# STorM32_BGC_mpu_module_v008.net
KiCad netlist of a schematic drawn in EAGLE
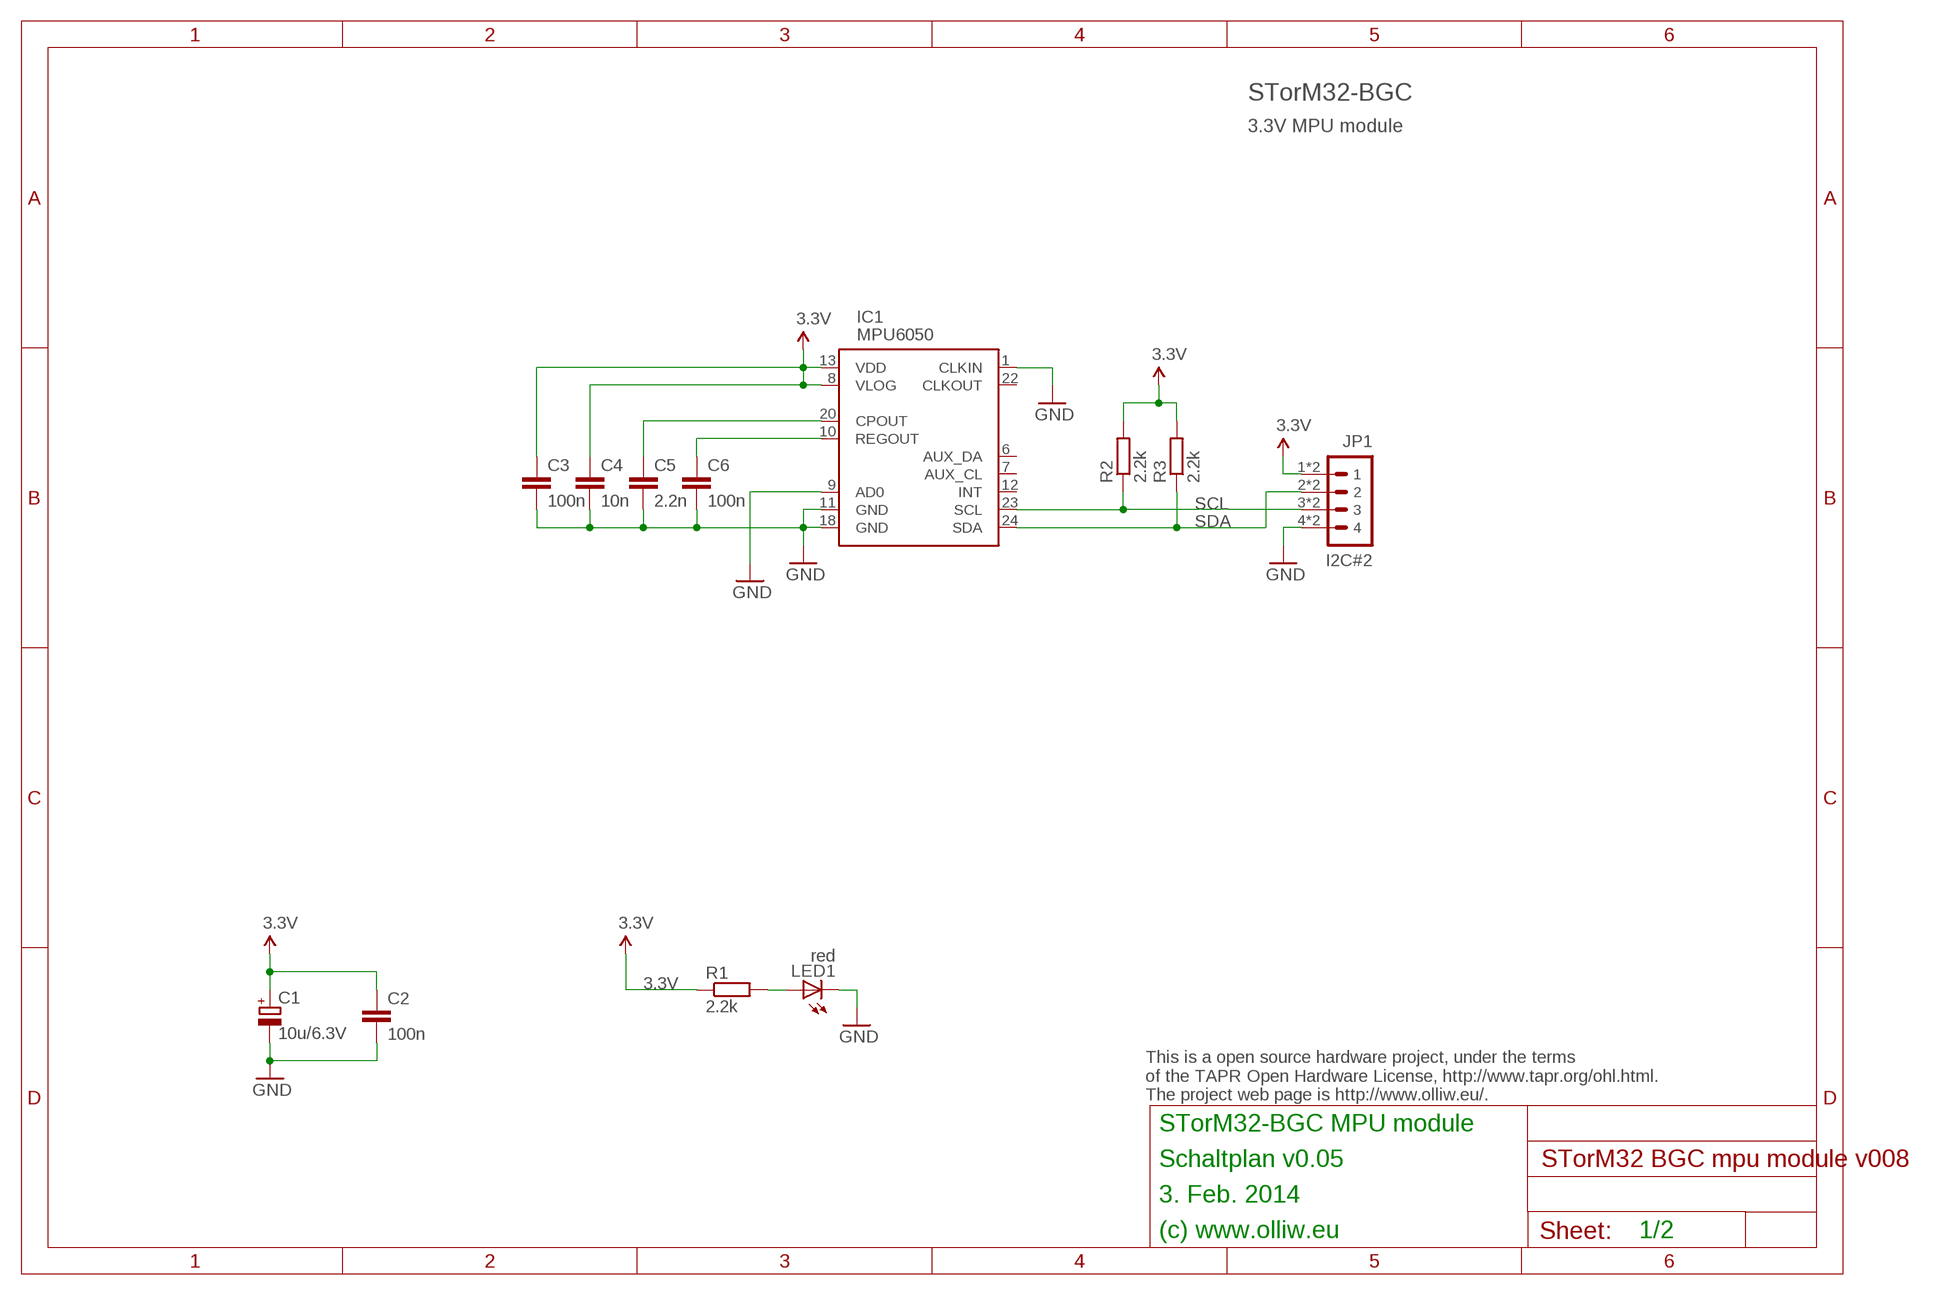
[diagram p0: schematic, sheet 1]

(export (version "E")
  (design (tool "Eeschema 10.0.6"))
  (components
    (comp (ref "C1")
      (value "10u/6.3V")
      (footprint "eagle-import:SMC_B")
      (libsource (lib "eagle-import") (part "CPOL-EUSMCB"))
    )
    (comp (ref "C2")
      (value "100n")
      (footprint "eagle-import:C0603")
      (libsource (lib "eagle-import") (part "C-EUC0603"))
    )
    (comp (ref "C3")
      (value "100n")
      (footprint "eagle-import:C0603")
      (libsource (lib "eagle-import") (part "C-EUC0603"))
    )
    (comp (ref "C4")
      (value "10n")
      (footprint "eagle-import:C0603")
      (libsource (lib "eagle-import") (part "C-EUC0603"))
    )
    (comp (ref "C5")
      (value "2.2n")
      (footprint "eagle-import:C0603")
      (libsource (lib "eagle-import") (part "C-EUC0603"))
    )
    (comp (ref "C6")
      (value "100n")
      (footprint "eagle-import:C0603")
      (libsource (lib "eagle-import") (part "C-EUC0603"))
    )
    (comp (ref "IC1")
      (value "MPU6050")
      (footprint "eagle-import:QFN-24")
      (libsource (lib "eagle-import") (part "IMU3000"))
    )
    (comp (ref "JP1")
      (value "I2C#2")
      (footprint "eagle-import:MOLEX-53261-04-SMD-BOTH")
      (libsource (lib "eagle-import") (part "P4X1_1P27MOLEX-BOTH"))
    )
    (comp (ref "LED1")
      (value "red")
      (footprint "eagle-import:CHIPLED_0603")
      (libsource (lib "eagle-import") (part "LEDCHIPLED_0603"))
    )
    (comp (ref "R1")
      (value "2.2k")
      (footprint "eagle-import:R0603")
      (libsource (lib "eagle-import") (part "R-EU_R0603"))
    )
    (comp (ref "R2")
      (value "2.2k")
      (footprint "eagle-import:R0603")
      (libsource (lib "eagle-import") (part "R-EU_R0603"))
    )
    (comp (ref "R3")
      (value "2.2k")
      (footprint "eagle-import:R0603")
      (libsource (lib "eagle-import") (part "R-EU_R0603"))
    )
  )
  (nets
    (net (code "1") (name "/SCL") (class "Default")
      (node (ref "IC1") (pin "23") (pinfunction "SCL_23") (pintype "bidirectional"))
      (node (ref "JP1") (pin "3") (pinfunction "3_3") (pintype "passive"))
      (node (ref "JP1") (pin "7") (pinfunction "3_7") (pintype "passive"))
      (node (ref "R2") (pin "1") (pinfunction "1_1") (pintype "passive"))
    )
    (net (code "2") (name "/SDA") (class "Default")
      (node (ref "IC1") (pin "24") (pinfunction "SDA_24") (pintype "bidirectional"))
      (node (ref "JP1") (pin "2") (pinfunction "2_2") (pintype "passive"))
      (node (ref "JP1") (pin "6") (pinfunction "2_6") (pintype "passive"))
      (node (ref "R3") (pin "1") (pinfunction "1_1") (pintype "passive"))
    )
    (net (code "3") (name "3.3V") (class "Default")
      (node (ref "C1") (pin "+") (pinfunction "+_+") (pintype "passive"))
      (node (ref "C2") (pin "1") (pinfunction "1_1") (pintype "passive"))
      (node (ref "C3") (pin "1") (pinfunction "1_1") (pintype "passive"))
      (node (ref "C4") (pin "1") (pinfunction "1_1") (pintype "passive"))
      (node (ref "IC1") (pin "13") (pinfunction "VDD_13") (pintype "bidirectional"))
      (node (ref "IC1") (pin "8") (pinfunction "VLOG_8") (pintype "bidirectional"))
      (node (ref "JP1") (pin "1") (pinfunction "1_1") (pintype "passive"))
      (node (ref "JP1") (pin "5") (pinfunction "1_5") (pintype "passive"))
      (node (ref "R1") (pin "1") (pinfunction "1_1") (pintype "passive"))
      (node (ref "R2") (pin "2") (pinfunction "2_2") (pintype "passive"))
      (node (ref "R3") (pin "2") (pinfunction "2_2") (pintype "passive"))
    )
    (net (code "4") (name "GND") (class "Default")
      (node (ref "C1") (pin "-") (pinfunction "-_-") (pintype "passive"))
      (node (ref "C2") (pin "2") (pinfunction "2_2") (pintype "passive"))
      (node (ref "C3") (pin "2") (pinfunction "2_2") (pintype "passive"))
      (node (ref "C4") (pin "2") (pinfunction "2_2") (pintype "passive"))
      (node (ref "C5") (pin "2") (pinfunction "2_2") (pintype "passive"))
      (node (ref "C6") (pin "2") (pinfunction "2_2") (pintype "passive"))
      (node (ref "IC1") (pin "1") (pinfunction "CLKIN_1") (pintype "bidirectional"))
      (node (ref "IC1") (pin "11") (pinfunction "GND_11") (pintype "bidirectional"))
      (node (ref "IC1") (pin "18") (pinfunction "GND_18") (pintype "bidirectional"))
      (node (ref "IC1") (pin "9") (pinfunction "AD0_9") (pintype "bidirectional"))
      (node (ref "JP1") (pin "4") (pinfunction "4_4") (pintype "passive"))
      (node (ref "JP1") (pin "8") (pinfunction "4_8") (pintype "passive"))
      (node (ref "LED1") (pin "C") (pinfunction "C_C") (pintype "passive"))
    )
    (net (code "5") (name "Net-(IC1-CPOUT)") (class "Default")
      (node (ref "C5") (pin "1") (pinfunction "1_1") (pintype "passive"))
      (node (ref "IC1") (pin "20") (pinfunction "CPOUT_20") (pintype "bidirectional"))
    )
    (net (code "6") (name "Net-(IC1-REGOUT)") (class "Default")
      (node (ref "C6") (pin "1") (pinfunction "1_1") (pintype "passive"))
      (node (ref "IC1") (pin "10") (pinfunction "REGOUT_10") (pintype "bidirectional"))
    )
    (net (code "7") (name "Net-(LED1-PadA)") (class "Default")
      (node (ref "LED1") (pin "A") (pinfunction "A_A") (pintype "passive"))
      (node (ref "R1") (pin "2") (pinfunction "2_2") (pintype "passive"))
    )
    (net (code "8") (name "unconnected-(IC1-AUX_CL-Pad7)") (class "Default")
      (node (ref "IC1") (pin "7") (pinfunction "AUX_CL_7") (pintype "bidirectional"))
    )
    (net (code "9") (name "unconnected-(IC1-AUX_DA-Pad6)") (class "Default")
      (node (ref "IC1") (pin "6") (pinfunction "AUX_DA_6") (pintype "bidirectional"))
    )
    (net (code "10") (name "unconnected-(IC1-CLKOUT-Pad22)") (class "Default")
      (node (ref "IC1") (pin "22") (pinfunction "CLKOUT_22") (pintype "bidirectional"))
    )
    (net (code "11") (name "unconnected-(IC1-INT-Pad12)") (class "Default")
      (node (ref "IC1") (pin "12") (pinfunction "INT_12") (pintype "bidirectional"))
    )
  )
)
